# ao.net
KiCad netlist of a schematic drawn in Altium Designer
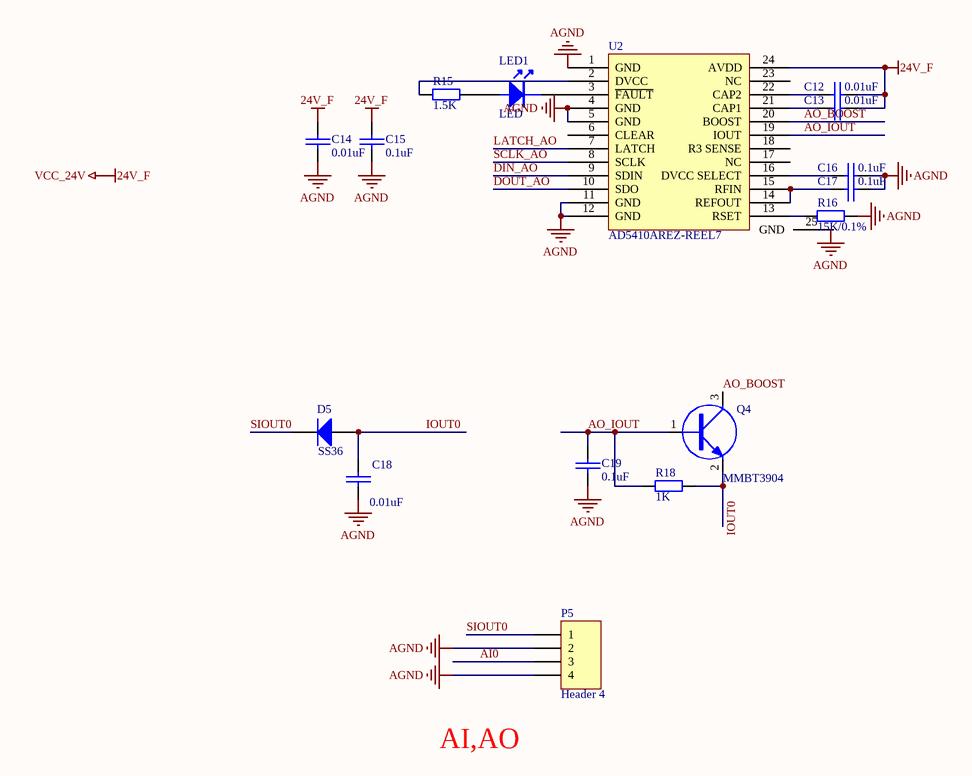
[diagram p0: ao.SchDoc]

(export (version "E")
  (design (tool "Eeschema 10.0.6"))
  (components
    (comp (ref "C12")
      (value "0.01uF")
      (footprint "0603C")
      (description "Capacitor")
      (libsource (lib "*") (part "CAP"))
    )
    (comp (ref "C13")
      (value "0.01uF")
      (footprint "0603C")
      (description "Capacitor")
      (libsource (lib "*") (part "CAP"))
    )
    (comp (ref "C14")
      (value "0.01uF")
      (footprint "0603C")
      (description "Capacitor")
      (libsource (lib "*") (part "CAP"))
    )
    (comp (ref "C15")
      (value "0.1uF")
      (footprint "0603C")
      (description "Capacitor")
      (libsource (lib "*") (part "CAP"))
    )
    (comp (ref "C16")
      (value "0.1uF")
      (footprint "0603C")
      (description "Capacitor")
      (libsource (lib "*") (part "CAP"))
    )
    (comp (ref "C17")
      (value "0.1uF")
      (footprint "0603C")
      (description "Capacitor")
      (libsource (lib "*") (part "CAP"))
    )
    (comp (ref "C18")
      (value "0.01uF")
      (footprint "0603C")
      (description "Capacitor")
      (libsource (lib "*") (part "CAP"))
    )
    (comp (ref "C19")
      (value "0.1uF")
      (footprint "0603C")
      (description "Capacitor")
      (libsource (lib "*") (part "CAP"))
    )
    (comp (ref "D5")
      (value "SS36")
      (footprint "sma")
      (description "1 Amp General Purpose Rectifier")
      (fields (field (name "PUBLISHER") "Altium Limited"))
      (libsource (lib "Miscellaneous Devices") (part "1N4001"))
    )
    (comp (ref "LED1") (value "LED") (footprint "0603LED") (libsource (lib "*") (part "LED")))
    (comp (ref "P5")
      (value "Header 4")
      (footprint "HDR1X4")
      (description "Header, 4-Pin")
      (fields (field (name "PUBLISHER") "Altium Limited"))
      (libsource (lib "Miscellaneous Connectors") (part "Header 4"))
    )
    (comp (ref "Q4")
      (value "MMBT3904")
      (footprint "SOT23-3")
      (libsource (lib "CenLib") (part "NPN_MMBT3904"))
    )
    (comp (ref "R15") (value "1.5K") (footprint "0603R") (libsource (lib "MQlibrary") (part "Res0805M")))
    (comp (ref "R16") (value "15K/0.1%") (footprint "0603R") (libsource (lib "MQlibrary") (part "Res0805M")))
    (comp (ref "R18") (value "1K") (footprint "0603R") (libsource (lib "MQlibrary") (part "Res0805M")))
    (comp (ref "U2")
      (value "AD5410AREZ-REEL7")
      (footprint "AD5410AREZ-REEL7")
      (libsource (lib "Schlib1") (part "AD5410AREZ-REEL7"))
    )
  )
  (nets
    (net (code "2") (name "/AI0") (class "Default")
      (node (ref "P5") (pin "3") (pinfunction "3_3") (pintype "passive"))
    )
    (net (code "3") (name "/AO_BOOST") (class "Default")
      (node (ref "Q4") (pin "3") (pinfunction "C_3") (pintype "passive"))
      (node (ref "U2") (pin "20") (pinfunction "BOOST_20") (pintype "passive"))
    )
    (net (code "4") (name "/AO_IOUT") (class "Default")
      (node (ref "C19") (pin "2") (pinfunction "2_2") (pintype "passive"))
      (node (ref "Q4") (pin "1") (pinfunction "B_1") (pintype "passive"))
      (node (ref "R18") (pin "1") (pinfunction "1_1") (pintype "passive"))
      (node (ref "U2") (pin "19") (pinfunction "IOUT_19") (pintype "passive"))
    )
    (net (code "5") (name "/DIN_AO") (class "Default")
      (node (ref "U2") (pin "9") (pinfunction "SDIN_9") (pintype "passive"))
    )
    (net (code "6") (name "/DOUT_AO") (class "Default")
      (node (ref "U2") (pin "10") (pinfunction "SDO_10") (pintype "passive"))
    )
    (net (code "7") (name "/IOUT0") (class "Default")
      (node (ref "C18") (pin "2") (pinfunction "2_2") (pintype "passive"))
      (node (ref "D5") (pin "1") (pinfunction "A_1") (pintype "passive"))
      (node (ref "Q4") (pin "2") (pinfunction "E_2") (pintype "passive"))
      (node (ref "R18") (pin "2") (pinfunction "2_2") (pintype "passive"))
    )
    (net (code "8") (name "/LATCH_AO") (class "Default")
      (node (ref "U2") (pin "7") (pinfunction "LATCH_7") (pintype "passive"))
    )
    (net (code "9") (name "/SCLK_AO") (class "Default")
      (node (ref "U2") (pin "8") (pinfunction "SCLK_8") (pintype "passive"))
    )
    (net (code "10") (name "/SIOUT0") (class "Default")
      (node (ref "D5") (pin "2") (pinfunction "K_2") (pintype "passive"))
      (node (ref "P5") (pin "1") (pinfunction "1_1") (pintype "passive"))
    )
    (net (code "11") (name "24V_F") (class "Default")
      (node (ref "C12") (pin "2") (pinfunction "2_2") (pintype "passive"))
      (node (ref "C13") (pin "2") (pinfunction "2_2") (pintype "passive"))
      (node (ref "C14") (pin "2") (pinfunction "2_2") (pintype "passive"))
      (node (ref "C15") (pin "2") (pinfunction "2_2") (pintype "passive"))
      (node (ref "U2") (pin "24") (pinfunction "AVDD_24") (pintype "passive"))
    )
    (net (code "12") (name "AGND") (class "Default")
      (node (ref "C14") (pin "1") (pinfunction "1_1") (pintype "passive"))
      (node (ref "C15") (pin "1") (pinfunction "1_1") (pintype "passive"))
      (node (ref "C16") (pin "2") (pinfunction "2_2") (pintype "passive"))
      (node (ref "C17") (pin "2") (pinfunction "2_2") (pintype "passive"))
      (node (ref "C18") (pin "1") (pinfunction "1_1") (pintype "passive"))
      (node (ref "C19") (pin "1") (pinfunction "1_1") (pintype "passive"))
      (node (ref "P5") (pin "2") (pinfunction "2_2") (pintype "passive"))
      (node (ref "P5") (pin "4") (pinfunction "4_4") (pintype "passive"))
      (node (ref "R16") (pin "2") (pinfunction "2_2") (pintype "passive"))
      (node (ref "U2") (pin "1") (pinfunction "GND_1") (pintype "passive"))
      (node (ref "U2") (pin "11") (pinfunction "GND_11") (pintype "passive"))
      (node (ref "U2") (pin "12") (pinfunction "GND_12") (pintype "passive"))
      (node (ref "U2") (pin "4") (pinfunction "GND_4") (pintype "passive"))
      (node (ref "U2") (pin "5") (pinfunction "GND_5") (pintype "passive"))
    )
    (net (code "13") (name "Net-(LED1-Pad1)") (class "Default")
      (node (ref "LED1") (pin "1") (pinfunction "1_1") (pintype "passive"))
      (node (ref "R15") (pin "2") (pinfunction "2_2") (pintype "passive"))
    )
    (net (code "14") (name "Net-(U2-CAP1)") (class "Default")
      (node (ref "C13") (pin "1") (pinfunction "1_1") (pintype "passive"))
      (node (ref "U2") (pin "21") (pinfunction "CAP1_21") (pintype "passive"))
    )
    (net (code "15") (name "Net-(U2-CAP2)") (class "Default")
      (node (ref "C12") (pin "1") (pinfunction "1_1") (pintype "passive"))
      (node (ref "U2") (pin "22") (pinfunction "CAP2_22") (pintype "passive"))
    )
    (net (code "16") (name "Net-(U2-DVCC)") (class "Default")
      (node (ref "R15") (pin "1") (pinfunction "1_1") (pintype "passive"))
      (node (ref "U2") (pin "2") (pinfunction "DVCC_2") (pintype "passive"))
    )
    (net (code "17") (name "Net-(U2-DVCC_SELECT)") (class "Default")
      (node (ref "C16") (pin "1") (pinfunction "1_1") (pintype "passive"))
      (node (ref "U2") (pin "16") (pinfunction "DVCC_SELECT_16") (pintype "passive"))
    )
    (net (code "18") (name "Net-(U2-REFOUT)") (class "Default")
      (node (ref "C17") (pin "1") (pinfunction "1_1") (pintype "passive"))
      (node (ref "U2") (pin "14") (pinfunction "REFOUT_14") (pintype "passive"))
      (node (ref "U2") (pin "15") (pinfunction "RFIN_15") (pintype "passive"))
    )
    (net (code "19") (name "Net-(U2-RSET)") (class "Default")
      (node (ref "R16") (pin "1") (pinfunction "1_1") (pintype "passive"))
      (node (ref "U2") (pin "13") (pinfunction "RSET_13") (pintype "passive"))
    )
    (net (code "20") (name "Net-(U2-~{FAULT})") (class "Default")
      (node (ref "LED1") (pin "2") (pinfunction "2_2") (pintype "passive"))
      (node (ref "U2") (pin "3") (pinfunction "~{FAULT}_3") (pintype "passive"))
    )
    (net (code "21") (name "unconnected-(U2-CLEAR-Pad6)") (class "Default")
      (node (ref "U2") (pin "6") (pinfunction "CLEAR_6") (pintype "passive"))
    )
    (net (code "22") (name "unconnected-(U2-GND-Pad25)") (class "Default")
      (node (ref "U2") (pin "25") (pinfunction "GND_25") (pintype "passive"))
    )
    (net (code "23") (name "unconnected-(U2-NC-Pad17)") (class "Default")
      (node (ref "U2") (pin "17") (pinfunction "NC_17") (pintype "passive"))
    )
    (net (code "24") (name "unconnected-(U2-NC-Pad23)") (class "Default")
      (node (ref "U2") (pin "23") (pinfunction "NC_23") (pintype "passive"))
    )
    (net (code "25") (name "unconnected-(U2-R3_SENSE-Pad18)") (class "Default")
      (node (ref "U2") (pin "18") (pinfunction "R3_SENSE_18") (pintype "passive"))
    )
  )
)
